# ADS_2.net
KiCad netlist of a schematic drawn in Altium Designer
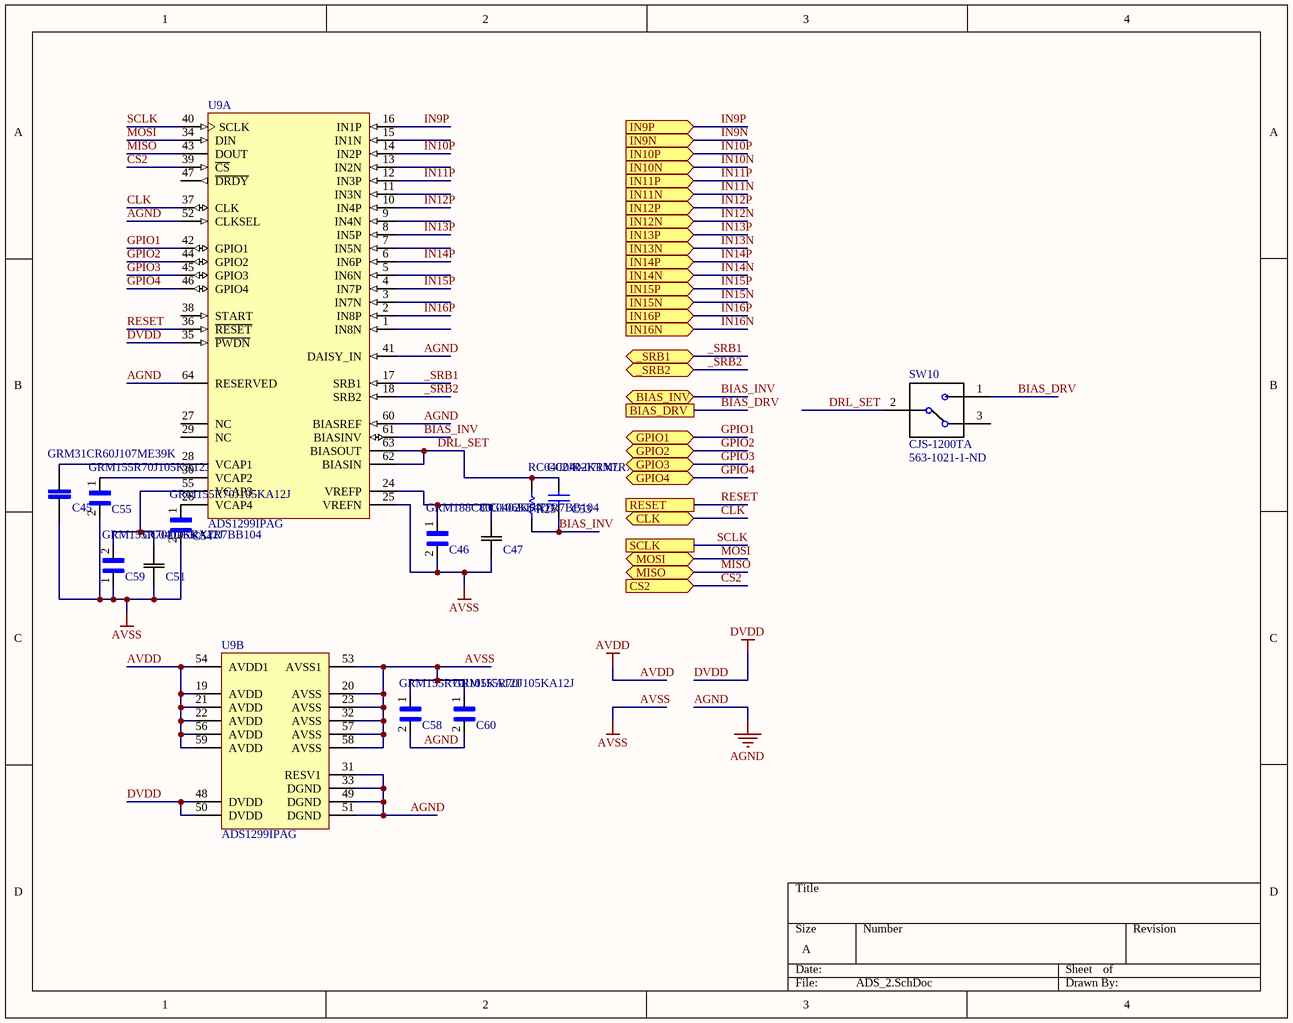
[diagram p0: ADS_2.SchDoc]

(export (version "E")
  (design (tool "Eeschema 10.0.6"))
  (components
    (comp (ref "C45")
      (value "GRM31CR60J107ME39K")
      (footprint "*CAPC3216X190")
      (description "MURATA - GRM31CR60J107ME39K - COND, 100µF, 6.3V, 20%, X5R, 1206")
      (fields (field (name "TOLERANCE") "20%") (field (name "VOLTAGE") "6.3V"))
      (libsource (lib "EE_smallOB_BW_v1.0") (part "GRM31CR60J107ME39K"))
    )
    (comp (ref "C46")
      (value "GRM188C80G106KE47D")
      (footprint "*CAPC1608X90N")
      (description "CAP CER 10UF 4V X6S 0603")
      (fields (field (name "TOLERANCE") "10%"))
      (libsource (lib "EE_smallOB_BW_v1.0") (part "GRM188C80G106KE47D"))
    )
    (comp (ref "C47")
      (value "CC0402KRX7R7BB104")
      (footprint "YAG_CC0402")
      (description "CAP CER 0.1UF 16V X7R 0402")
      (fields (field (name "TOLERANCE") "10%") (field (name "VOLTAGE") "16V"))
      (libsource (lib "EE_smallOB_BW_v1.0") (part "CC0402KRX7R7BB104"))
    )
    (comp (ref "C51")
      (value "CC0402KRX7R7BB104")
      (footprint "YAG_CC0402")
      (description "CAP CER 0.1UF 16V X7R 0402")
      (fields (field (name "TOLERANCE") "10%") (field (name "VOLTAGE") "16V"))
      (libsource (lib "EE_smallOB_BW_v1.0") (part "CC0402KRX7R7BB104"))
    )
    (comp (ref "C53")
      (value "CC0402KRX7R7BB102")
      (footprint "CAPC1005X55X23NL05T08")
      (description "CAP CER 1000PF 16V X7R 0402")
      (fields (field (name "TOLERANCE") "10%"))
      (libsource (lib "EE_smallOB_BW_v1.0") (part "CC0402KRX7R7BB102"))
    )
    (comp (ref "C54")
      (value "GRM155R70J105KA12J")
      (footprint "*CAPC1005X55N")
      (description "CAP CER 1UF 6.3V X7R 0402")
      (fields (field (name "TOLERANCE") "10%"))
      (libsource (lib "EE_smallOB_BW_v1.0") (part "GRM155R70J105KA12J"))
    )
    (comp (ref "C55")
      (value "GRM155R70J105KA12J")
      (footprint "*CAPC1005X55N")
      (description "CAP CER 1UF 6.3V X7R 0402")
      (fields (field (name "TOLERANCE") "10%"))
      (libsource (lib "EE_smallOB_BW_v1.0") (part "GRM155R70J105KA12J"))
    )
    (comp (ref "C58")
      (value "GRM155R70J105KA12J")
      (footprint "*CAPC1005X55N")
      (description "CAP CER 1UF 6.3V X7R 0402")
      (fields (field (name "TOLERANCE") "10%"))
      (libsource (lib "EE_smallOB_BW_v1.0") (part "GRM155R70J105KA12J"))
    )
    (comp (ref "C59")
      (value "GRM155R70J105KA12J")
      (footprint "*CAPC1005X55N")
      (description "CAP CER 1UF 6.3V X7R 0402")
      (fields (field (name "TOLERANCE") "10%"))
      (libsource (lib "EE_smallOB_BW_v1.0") (part "GRM155R70J105KA12J"))
    )
    (comp (ref "C60")
      (value "GRM155R70J105KA12J")
      (footprint "*CAPC1005X55N")
      (description "CAP CER 1UF 6.3V X7R 0402")
      (fields (field (name "TOLERANCE") "10%"))
      (libsource (lib "EE_smallOB_BW_v1.0") (part "GRM155R70J105KA12J"))
    )
    (comp (ref "R25")
      (value "RC0402JR-071ML")
      (footprint "RESC1005X40X25NL05T10")
      (description "RES SMD 1M OHM 5% 1/16W 0402")
      (fields (field (name "TOLERANCE") "5%"))
      (libsource (lib "EE_smallOB_BW_v1.0") (part "RC0402JR-071ML"))
    )
    (comp (ref "SW10")
      (value "CJS-1200TA")
      (footprint "*SW_CJS-1200TA")
      (description "SWITCH SLIDE SPDT 100MA 6V")
      (fields (field (name "SUPPLIER PART NUMBER 1") "563-1021-1-ND"))
      (libsource (lib "EE_smallOB_BW_v1.0") (part "CJS-1200TA"))
    )
    (comp (ref "U9")
      (value "ADS1299IPAG")
      (footprint "PAG0064A_N")
      (description "IC AFE 24BIT 16KSPS LN 64TQFP")
      (libsource (lib "EE_smallOB_BW_v1.0") (part "ADS1299IPAG"))
    )
  )
  (nets
    (net (code "1") (name "/BIAS_DRV") (class "Default")
      (node (ref "SW10") (pin "1") (pinfunction "1_1") (pintype "passive"))
    )
    (net (code "2") (name "/BIAS_INV") (class "Default")
      (node (ref "C53") (pin "2") (pinfunction "2_2") (pintype "passive"))
      (node (ref "R25") (pin "2") (pinfunction "2_2") (pintype "passive"))
      (node (ref "U9") (pin "61") (pinfunction "BIASINV_61") (pintype "bidirectional"))
    )
    (net (code "3") (name "/CLK") (class "Default")
      (node (ref "U9") (pin "37") (pinfunction "CLK_37") (pintype "bidirectional"))
    )
    (net (code "4") (name "/CS2") (class "Default")
      (node (ref "U9") (pin "39") (pinfunction "~{CS}_39") (pintype "input"))
    )
    (net (code "5") (name "/DRL_SET") (class "Default")
      (node (ref "C53") (pin "1") (pinfunction "1_1") (pintype "passive"))
      (node (ref "R25") (pin "1") (pinfunction "1_1") (pintype "passive"))
      (node (ref "SW10") (pin "2") (pinfunction "2_2") (pintype "passive"))
      (node (ref "U9") (pin "62") (pinfunction "BIASIN_62") (pintype "passive"))
      (node (ref "U9") (pin "63") (pinfunction "BIASOUT_63") (pintype "passive"))
    )
    (net (code "6") (name "/GPIO1") (class "Default")
      (node (ref "U9") (pin "42") (pinfunction "GPIO1_42") (pintype "bidirectional"))
    )
    (net (code "7") (name "/GPIO2") (class "Default")
      (node (ref "U9") (pin "44") (pinfunction "GPIO2_44") (pintype "bidirectional"))
    )
    (net (code "8") (name "/GPIO3") (class "Default")
      (node (ref "U9") (pin "45") (pinfunction "GPIO3_45") (pintype "bidirectional"))
    )
    (net (code "9") (name "/GPIO4") (class "Default")
      (node (ref "U9") (pin "46") (pinfunction "GPIO4_46") (pintype "bidirectional"))
    )
    (net (code "11") (name "/IN9P") (class "Default")
      (node (ref "U9") (pin "16") (pinfunction "IN1P_16") (pintype "input"))
    )
    (net (code "13") (name "/IN10P") (class "Default")
      (node (ref "U9") (pin "14") (pinfunction "IN2P_14") (pintype "input"))
    )
    (net (code "15") (name "/IN11P") (class "Default")
      (node (ref "U9") (pin "12") (pinfunction "IN3P_12") (pintype "input"))
    )
    (net (code "17") (name "/IN12P") (class "Default")
      (node (ref "U9") (pin "10") (pinfunction "IN4P_10") (pintype "input"))
    )
    (net (code "19") (name "/IN13P") (class "Default")
      (node (ref "U9") (pin "8") (pinfunction "IN5P_8") (pintype "input"))
    )
    (net (code "21") (name "/IN14P") (class "Default")
      (node (ref "U9") (pin "6") (pinfunction "IN6P_6") (pintype "input"))
    )
    (net (code "23") (name "/IN15P") (class "Default")
      (node (ref "U9") (pin "4") (pinfunction "IN7P_4") (pintype "input"))
    )
    (net (code "25") (name "/IN16P") (class "Default")
      (node (ref "U9") (pin "2") (pinfunction "IN8P_2") (pintype "input"))
    )
    (net (code "26") (name "/MISO") (class "Default")
      (node (ref "U9") (pin "43") (pinfunction "DOUT_43") (pintype "tri_state"))
    )
    (net (code "27") (name "/MOSI") (class "Default")
      (node (ref "U9") (pin "34") (pinfunction "DIN_34") (pintype "input"))
    )
    (net (code "28") (name "/RESET") (class "Default")
      (node (ref "U9") (pin "36") (pinfunction "~{RESET}_36") (pintype "input"))
    )
    (net (code "29") (name "/SCLK") (class "Default")
      (node (ref "U9") (pin "40") (pinfunction "SCLK_40") (pintype "input"))
    )
    (net (code "30") (name "/_SRB1") (class "Default")
      (node (ref "U9") (pin "17") (pinfunction "SRB1_17") (pintype "input"))
    )
    (net (code "31") (name "/_SRB2") (class "Default")
      (node (ref "U9") (pin "18") (pinfunction "SRB2_18") (pintype "input"))
    )
    (net (code "32") (name "AGND") (class "Default")
      (node (ref "C58") (pin "2") (pinfunction "2_2") (pintype "passive"))
      (node (ref "C60") (pin "2") (pinfunction "2_2") (pintype "passive"))
      (node (ref "U9") (pin "31") (pinfunction "RESV1_31") (pintype "power_in"))
      (node (ref "U9") (pin "33") (pinfunction "DGND_33") (pintype "power_in"))
      (node (ref "U9") (pin "41") (pinfunction "DAISY_IN_41") (pintype "input"))
      (node (ref "U9") (pin "49") (pinfunction "DGND_49") (pintype "power_in"))
      (node (ref "U9") (pin "51") (pinfunction "DGND_51") (pintype "power_in"))
      (node (ref "U9") (pin "52") (pinfunction "CLKSEL_52") (pintype "input"))
      (node (ref "U9") (pin "60") (pinfunction "BIASREF_60") (pintype "input"))
      (node (ref "U9") (pin "64") (pinfunction "RESERVED_64") (pintype "passive"))
    )
    (net (code "33") (name "AVDD") (class "Default")
      (node (ref "U9") (pin "19") (pinfunction "AVDD_19") (pintype "power_in"))
      (node (ref "U9") (pin "21") (pinfunction "AVDD_21") (pintype "power_in"))
      (node (ref "U9") (pin "22") (pinfunction "AVDD_22") (pintype "power_in"))
      (node (ref "U9") (pin "54") (pinfunction "AVDD1_54") (pintype "power_in"))
      (node (ref "U9") (pin "56") (pinfunction "AVDD_56") (pintype "power_in"))
      (node (ref "U9") (pin "59") (pinfunction "AVDD_59") (pintype "power_in"))
    )
    (net (code "34") (name "AVSS") (class "Default")
      (node (ref "C45") (pin "2") (pinfunction "2_2") (pintype "passive"))
      (node (ref "C46") (pin "2") (pinfunction "2_2") (pintype "passive"))
      (node (ref "C47") (pin "2") (pinfunction "2_2") (pintype "passive"))
      (node (ref "C51") (pin "1") (pinfunction "1_1") (pintype "passive"))
      (node (ref "C54") (pin "2") (pinfunction "2_2") (pintype "passive"))
      (node (ref "C55") (pin "2") (pinfunction "2_2") (pintype "passive"))
      (node (ref "C58") (pin "1") (pinfunction "1_1") (pintype "passive"))
      (node (ref "C59") (pin "1") (pinfunction "1_1") (pintype "passive"))
      (node (ref "C60") (pin "1") (pinfunction "1_1") (pintype "passive"))
      (node (ref "U9") (pin "20") (pinfunction "AVSS_20") (pintype "power_in"))
      (node (ref "U9") (pin "23") (pinfunction "AVSS_23") (pintype "power_in"))
      (node (ref "U9") (pin "25") (pinfunction "VREFN_25") (pintype "passive"))
      (node (ref "U9") (pin "32") (pinfunction "AVSS_32") (pintype "power_in"))
      (node (ref "U9") (pin "53") (pinfunction "AVSS1_53") (pintype "power_in"))
      (node (ref "U9") (pin "57") (pinfunction "AVSS_57") (pintype "power_in"))
      (node (ref "U9") (pin "58") (pinfunction "AVSS_58") (pintype "power_in"))
    )
    (net (code "35") (name "DVDD") (class "Default")
      (node (ref "U9") (pin "35") (pinfunction "~{PWDN}_35") (pintype "input"))
      (node (ref "U9") (pin "48") (pinfunction "DVDD_48") (pintype "power_in"))
      (node (ref "U9") (pin "50") (pinfunction "DVDD_50") (pintype "power_in"))
    )
    (net (code "36") (name "Net-(U9A-VCAP1)") (class "Default")
      (node (ref "C45") (pin "1") (pinfunction "1_1") (pintype "passive"))
      (node (ref "U9") (pin "28") (pinfunction "VCAP1_28") (pintype "passive"))
    )
    (net (code "37") (name "Net-(U9A-VCAP2)") (class "Default")
      (node (ref "C55") (pin "1") (pinfunction "1_1") (pintype "passive"))
      (node (ref "U9") (pin "30") (pinfunction "VCAP2_30") (pintype "passive"))
    )
    (net (code "38") (name "Net-(U9A-VCAP3)") (class "Default")
      (node (ref "C51") (pin "2") (pinfunction "2_2") (pintype "passive"))
      (node (ref "C59") (pin "2") (pinfunction "2_2") (pintype "passive"))
      (node (ref "U9") (pin "55") (pinfunction "VCAP3_55") (pintype "passive"))
    )
    (net (code "39") (name "Net-(U9A-VCAP4)") (class "Default")
      (node (ref "C54") (pin "1") (pinfunction "1_1") (pintype "passive"))
      (node (ref "U9") (pin "26") (pinfunction "VCAP4_26") (pintype "passive"))
    )
    (net (code "40") (name "Net-(U9A-VREFP)") (class "Default")
      (node (ref "C46") (pin "1") (pinfunction "1_1") (pintype "passive"))
      (node (ref "C47") (pin "1") (pinfunction "1_1") (pintype "passive"))
      (node (ref "U9") (pin "24") (pinfunction "VREFP_24") (pintype "passive"))
    )
    (net (code "41") (name "unconnected-(SW10-Pad3)") (class "Default")
      (node (ref "SW10") (pin "3") (pinfunction "3_3") (pintype "passive"))
    )
    (net (code "42") (name "unconnected-(U9A-IN1N-Pad15)") (class "Default")
      (node (ref "U9") (pin "15") (pinfunction "IN1N_15") (pintype "input"))
    )
    (net (code "43") (name "unconnected-(U9A-IN2N-Pad13)") (class "Default")
      (node (ref "U9") (pin "13") (pinfunction "IN2N_13") (pintype "input"))
    )
    (net (code "44") (name "unconnected-(U9A-IN3N-Pad11)") (class "Default")
      (node (ref "U9") (pin "11") (pinfunction "IN3N_11") (pintype "input"))
    )
    (net (code "45") (name "unconnected-(U9A-IN4N-Pad9)") (class "Default")
      (node (ref "U9") (pin "9") (pinfunction "IN4N_9") (pintype "input"))
    )
    (net (code "46") (name "unconnected-(U9A-IN5N-Pad7)") (class "Default")
      (node (ref "U9") (pin "7") (pinfunction "IN5N_7") (pintype "input"))
    )
    (net (code "47") (name "unconnected-(U9A-IN6N-Pad5)") (class "Default")
      (node (ref "U9") (pin "5") (pinfunction "IN6N_5") (pintype "input"))
    )
    (net (code "48") (name "unconnected-(U9A-IN7N-Pad3)") (class "Default")
      (node (ref "U9") (pin "3") (pinfunction "IN7N_3") (pintype "input"))
    )
    (net (code "49") (name "unconnected-(U9A-IN8N-Pad1)") (class "Default")
      (node (ref "U9") (pin "1") (pinfunction "IN8N_1") (pintype "input"))
    )
    (net (code "50") (name "unconnected-(U9A-NC-Pad27)") (class "Default")
      (node (ref "U9") (pin "27") (pinfunction "NC_27") (pintype "passive"))
    )
    (net (code "51") (name "unconnected-(U9A-NC-Pad29)") (class "Default")
      (node (ref "U9") (pin "29") (pinfunction "NC_29") (pintype "passive"))
    )
    (net (code "52") (name "unconnected-(U9A-START-Pad38)") (class "Default")
      (node (ref "U9") (pin "38") (pinfunction "START_38") (pintype "input"))
    )
    (net (code "53") (name "unconnected-(U9A-~{DRDY}-Pad47)") (class "Default")
      (node (ref "U9") (pin "47") (pinfunction "~{DRDY}_47") (pintype "output"))
    )
  )
)
